# micron_P6.net
KiCad netlist of a schematic drawn in Altium Designer
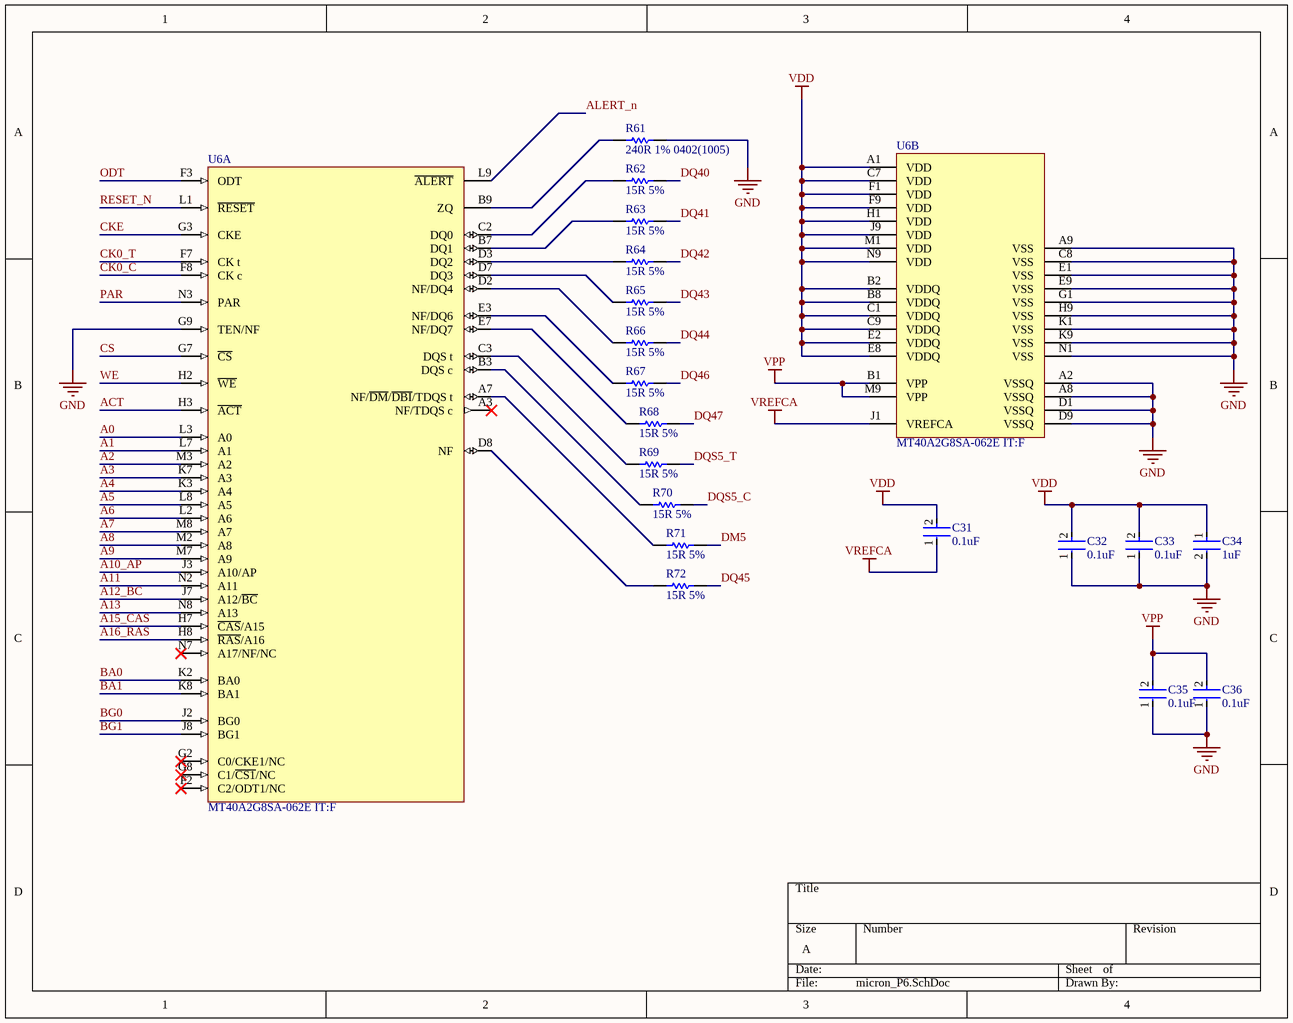
[diagram p0: micron_P6.SchDoc]

(export (version "E")
  (design (tool "Eeschema 10.0.6"))
  (components
    (comp (ref "C31")
      (value "0.1uF")
      (footprint "FP-GRM15-MFG")
      (description "CAP CER 0.1UF 16V X7R 0402")
      (fields (field (name "MANUFACTURER PART NUMBER") "GRM155R71C104KA88D") (field (name "TOLERANCE") "10%"))
      (libsource (lib "Altium Content Vault") (part "236180d848d6139a670b325ea6854c9"))
    )
    (comp (ref "C32")
      (value "0.1uF")
      (footprint "FP-GRM15-MFG")
      (description "CAP CER 0.1UF 16V X7R 0402")
      (fields (field (name "MANUFACTURER PART NUMBER") "GRM155R71C104KA88D") (field (name "TOLERANCE") "10%"))
      (libsource (lib "Altium Content Vault") (part "236180d848d6139a670b325ea6854c9"))
    )
    (comp (ref "C33")
      (value "0.1uF")
      (footprint "FP-GRM15-MFG")
      (description "CAP CER 0.1UF 16V X7R 0402")
      (fields (field (name "MANUFACTURER PART NUMBER") "GRM155R71C104KA88D") (field (name "TOLERANCE") "10%"))
      (libsource (lib "Altium Content Vault") (part "236180d848d6139a670b325ea6854c9"))
    )
    (comp (ref "C34")
      (value "1uF")
      (footprint "FP-CL511-IPC_C")
      (description "Cap Ceramic 1uF 10V X5R ±10% SMD 0402 +85°C Paper T/R")
      (fields (field (name "TOLERANCE") "10%"))
      (libsource (lib "Altium Content Vault") (part "b4654b650e69147ec39a6b967a45e02"))
    )
    (comp (ref "C35")
      (value "0.1uF")
      (footprint "FP-GRM15-MFG")
      (description "CAP CER 0.1UF 16V X7R 0402")
      (fields (field (name "MANUFACTURER PART NUMBER") "GRM155R71C104KA88D") (field (name "TOLERANCE") "10%"))
      (libsource (lib "Altium Content Vault") (part "236180d848d6139a670b325ea6854c9"))
    )
    (comp (ref "C36")
      (value "0.1uF")
      (footprint "FP-GRM15-MFG")
      (description "CAP CER 0.1UF 16V X7R 0402")
      (fields (field (name "MANUFACTURER PART NUMBER") "GRM155R71C104KA88D") (field (name "TOLERANCE") "10%"))
      (libsource (lib "Altium Content Vault") (part "236180d848d6139a670b325ea6854c9"))
    )
    (comp (ref "R61")
      (value "240R 1% 0402(1005)")
      (footprint "RESC0402(1005)_L")
      (description "240R 0.063W 1% 0402 (1005 Metric)  SMD")
      (fields (field (name "POWER") "0.063 W") (field (name "TOLERANCE") "1 %"))
      (libsource (lib "Altium Content Vault") (part "RES"))
    )
    (comp (ref "R62")
      (value "15R 5%")
      (footprint "RESC1005X40X25LL05T10")
      (fields (field (name "MANUFACTURER") "Yageo / Phycomp") (field (name "PART NUMBER") "RC0402FR-0715RL"))
      (libsource (lib "Altium Content Vault") (part "RES"))
    )
    (comp (ref "R63")
      (value "15R 5%")
      (footprint "RESC1005X40X25LL05T10")
      (fields (field (name "MANUFACTURER") "Yageo / Phycomp") (field (name "PART NUMBER") "RC0402FR-0715RL"))
      (libsource (lib "Altium Content Vault") (part "RES"))
    )
    (comp (ref "R64")
      (value "15R 5%")
      (footprint "RESC1005X40X25LL05T10")
      (fields (field (name "MANUFACTURER") "Yageo / Phycomp") (field (name "PART NUMBER") "RC0402FR-0715RL"))
      (libsource (lib "Altium Content Vault") (part "RES"))
    )
    (comp (ref "R65")
      (value "15R 5%")
      (footprint "RESC1005X40X25LL05T10")
      (fields (field (name "MANUFACTURER") "Yageo / Phycomp") (field (name "PART NUMBER") "RC0402FR-0715RL"))
      (libsource (lib "Altium Content Vault") (part "RES"))
    )
    (comp (ref "R66")
      (value "15R 5%")
      (footprint "RESC1005X40X25LL05T10")
      (fields (field (name "MANUFACTURER") "Yageo / Phycomp") (field (name "PART NUMBER") "RC0402FR-0715RL"))
      (libsource (lib "Altium Content Vault") (part "RES"))
    )
    (comp (ref "R67")
      (value "15R 5%")
      (footprint "RESC1005X40X25LL05T10")
      (fields (field (name "MANUFACTURER") "Yageo / Phycomp") (field (name "PART NUMBER") "RC0402FR-0715RL"))
      (libsource (lib "Altium Content Vault") (part "RES"))
    )
    (comp (ref "R68")
      (value "15R 5%")
      (footprint "RESC1005X40X25LL05T10")
      (fields (field (name "MANUFACTURER") "Yageo / Phycomp") (field (name "PART NUMBER") "RC0402FR-0715RL"))
      (libsource (lib "Altium Content Vault") (part "RES"))
    )
    (comp (ref "R69")
      (value "15R 5%")
      (footprint "RESC1005X40X25LL05T10")
      (fields (field (name "MANUFACTURER") "Yageo / Phycomp") (field (name "PART NUMBER") "RC0402FR-0715RL"))
      (libsource (lib "Altium Content Vault") (part "RES"))
    )
    (comp (ref "R70")
      (value "15R 5%")
      (footprint "RESC1005X40X25LL05T10")
      (fields (field (name "MANUFACTURER") "Yageo / Phycomp") (field (name "PART NUMBER") "RC0402FR-0715RL"))
      (libsource (lib "Altium Content Vault") (part "RES"))
    )
    (comp (ref "R71")
      (value "15R 5%")
      (footprint "RESC1005X40X25LL05T10")
      (fields (field (name "MANUFACTURER") "Yageo / Phycomp") (field (name "PART NUMBER") "RC0402FR-0715RL"))
      (libsource (lib "Altium Content Vault") (part "RES"))
    )
    (comp (ref "R72")
      (value "15R 5%")
      (footprint "RESC1005X40X25LL05T10")
      (fields (field (name "MANUFACTURER") "Yageo / Phycomp") (field (name "PART NUMBER") "RC0402FR-0715RL"))
      (libsource (lib "Altium Content Vault") (part "RES"))
    )
    (comp (ref "U6")
      (value "MT40A2G8SA-062E IT:F")
      (footprint "SA_MFG")
      (description "DRAMChip DDR4 SDRAM 16Gbit 2Gx8 1.2V 78-Pin FBGA Tray")
      (libsource (lib "Altium Content Vault") (part "d28cb998757b614ee3280f10a38a3b1"))
    )
  )
  (nets
    (net (code "1") (name "/A0") (class "Default")
      (node (ref "U6") (pin "L3") (pinfunction "A0_L3") (pintype "input"))
    )
    (net (code "2") (name "/A1") (class "Default")
      (node (ref "U6") (pin "L7") (pinfunction "A1_L7") (pintype "input"))
    )
    (net (code "3") (name "/A2") (class "Default")
      (node (ref "U6") (pin "M3") (pinfunction "A2_M3") (pintype "input"))
    )
    (net (code "4") (name "/A3") (class "Default")
      (node (ref "U6") (pin "K7") (pinfunction "A3_K7") (pintype "input"))
    )
    (net (code "5") (name "/A4") (class "Default")
      (node (ref "U6") (pin "K3") (pinfunction "A4_K3") (pintype "input"))
    )
    (net (code "6") (name "/A5") (class "Default")
      (node (ref "U6") (pin "L8") (pinfunction "A5_L8") (pintype "input"))
    )
    (net (code "7") (name "/A6") (class "Default")
      (node (ref "U6") (pin "L2") (pinfunction "A6_L2") (pintype "input"))
    )
    (net (code "8") (name "/A7") (class "Default")
      (node (ref "U6") (pin "M8") (pinfunction "A7_M8") (pintype "input"))
    )
    (net (code "9") (name "/A8") (class "Default")
      (node (ref "U6") (pin "M2") (pinfunction "A8_M2") (pintype "input"))
    )
    (net (code "10") (name "/A9") (class "Default")
      (node (ref "U6") (pin "M7") (pinfunction "A9_M7") (pintype "input"))
    )
    (net (code "11") (name "/A10_AP") (class "Default")
      (node (ref "U6") (pin "J3") (pinfunction "A10/AP_J3") (pintype "input"))
    )
    (net (code "12") (name "/A11") (class "Default")
      (node (ref "U6") (pin "N2") (pinfunction "A11_N2") (pintype "input"))
    )
    (net (code "13") (name "/A12_BC") (class "Default")
      (node (ref "U6") (pin "J7") (pinfunction "A12/~{BC}_J7") (pintype "input"))
    )
    (net (code "14") (name "/A13") (class "Default")
      (node (ref "U6") (pin "N8") (pinfunction "A13_N8") (pintype "input"))
    )
    (net (code "15") (name "/A15_CAS") (class "Default")
      (node (ref "U6") (pin "H7") (pinfunction "~{CAS}/A15_H7") (pintype "input"))
    )
    (net (code "16") (name "/A16_RAS") (class "Default")
      (node (ref "U6") (pin "H8") (pinfunction "~{RAS}/A16_H8") (pintype "input"))
    )
    (net (code "17") (name "/ACT") (class "Default")
      (node (ref "U6") (pin "H3") (pinfunction "~{ACT}_H3") (pintype "input"))
    )
    (net (code "18") (name "/ALERT_n") (class "Default")
      (node (ref "U6") (pin "L9") (pinfunction "~{ALERT}_L9") (pintype "open_collector"))
    )
    (net (code "19") (name "/BA0") (class "Default")
      (node (ref "U6") (pin "K2") (pinfunction "BA0_K2") (pintype "input"))
    )
    (net (code "20") (name "/BA1") (class "Default")
      (node (ref "U6") (pin "K8") (pinfunction "BA1_K8") (pintype "input"))
    )
    (net (code "21") (name "/BG0") (class "Default")
      (node (ref "U6") (pin "J2") (pinfunction "BG0_J2") (pintype "input"))
    )
    (net (code "22") (name "/BG1") (class "Default")
      (node (ref "U6") (pin "J8") (pinfunction "BG1_J8") (pintype "input"))
    )
    (net (code "23") (name "/CK0_C") (class "Default")
      (node (ref "U6") (pin "F8") (pinfunction "CK_c_F8") (pintype "input"))
    )
    (net (code "24") (name "/CK0_T") (class "Default")
      (node (ref "U6") (pin "F7") (pinfunction "CK_t_F7") (pintype "input"))
    )
    (net (code "25") (name "/CKE") (class "Default")
      (node (ref "U6") (pin "G3") (pinfunction "CKE_G3") (pintype "input"))
    )
    (net (code "26") (name "/CS") (class "Default")
      (node (ref "U6") (pin "G7") (pinfunction "~{CS}_G7") (pintype "input"))
    )
    (net (code "27") (name "/DM5") (class "Default")
      (node (ref "R71") (pin "2") (pinfunction "2_2") (pintype "passive"))
    )
    (net (code "28") (name "/DQ40") (class "Default")
      (node (ref "R62") (pin "2") (pinfunction "2_2") (pintype "passive"))
    )
    (net (code "29") (name "/DQ41") (class "Default")
      (node (ref "R63") (pin "2") (pinfunction "2_2") (pintype "passive"))
    )
    (net (code "30") (name "/DQ42") (class "Default")
      (node (ref "R64") (pin "2") (pinfunction "2_2") (pintype "passive"))
    )
    (net (code "31") (name "/DQ43") (class "Default")
      (node (ref "R65") (pin "2") (pinfunction "2_2") (pintype "passive"))
    )
    (net (code "32") (name "/DQ44") (class "Default")
      (node (ref "R66") (pin "2") (pinfunction "2_2") (pintype "passive"))
    )
    (net (code "33") (name "/DQ45") (class "Default")
      (node (ref "R72") (pin "2") (pinfunction "2_2") (pintype "passive"))
    )
    (net (code "34") (name "/DQ46") (class "Default")
      (node (ref "R67") (pin "2") (pinfunction "2_2") (pintype "passive"))
    )
    (net (code "35") (name "/DQ47") (class "Default")
      (node (ref "R68") (pin "2") (pinfunction "2_2") (pintype "passive"))
    )
    (net (code "36") (name "/DQS5_C") (class "Default")
      (node (ref "R70") (pin "2") (pinfunction "2_2") (pintype "passive"))
    )
    (net (code "37") (name "/DQS5_T") (class "Default")
      (node (ref "R69") (pin "2") (pinfunction "2_2") (pintype "passive"))
    )
    (net (code "38") (name "/ODT") (class "Default")
      (node (ref "U6") (pin "F3") (pinfunction "ODT_F3") (pintype "input"))
    )
    (net (code "39") (name "/PAR") (class "Default")
      (node (ref "U6") (pin "N3") (pinfunction "PAR_N3") (pintype "input"))
    )
    (net (code "40") (name "/RESET_N") (class "Default")
      (node (ref "U6") (pin "L1") (pinfunction "~{RESET}_L1") (pintype "input"))
    )
    (net (code "41") (name "/WE") (class "Default")
      (node (ref "U6") (pin "H2") (pinfunction "~{WE}_H2") (pintype "input"))
    )
    (net (code "42") (name "GND") (class "Default")
      (node (ref "C32") (pin "1") (pinfunction "1_1") (pintype "passive"))
      (node (ref "C33") (pin "1") (pinfunction "1_1") (pintype "passive"))
      (node (ref "C34") (pin "2") (pinfunction "2_2") (pintype "passive"))
      (node (ref "C35") (pin "1") (pinfunction "1_1") (pintype "passive"))
      (node (ref "C36") (pin "1") (pinfunction "1_1") (pintype "passive"))
      (node (ref "R61") (pin "2") (pinfunction "2_2") (pintype "passive"))
      (node (ref "U6") (pin "A2") (pinfunction "VSSQ_A2") (pintype "power_in"))
      (node (ref "U6") (pin "A8") (pinfunction "VSSQ_A8") (pintype "power_in"))
      (node (ref "U6") (pin "A9") (pinfunction "VSS_A9") (pintype "power_in"))
      (node (ref "U6") (pin "C8") (pinfunction "VSS_C8") (pintype "power_in"))
      (node (ref "U6") (pin "D1") (pinfunction "VSSQ_D1") (pintype "power_in"))
      (node (ref "U6") (pin "D9") (pinfunction "VSSQ_D9") (pintype "power_in"))
      (node (ref "U6") (pin "E1") (pinfunction "VSS_E1") (pintype "power_in"))
      (node (ref "U6") (pin "E9") (pinfunction "VSS_E9") (pintype "power_in"))
      (node (ref "U6") (pin "G1") (pinfunction "VSS_G1") (pintype "power_in"))
      (node (ref "U6") (pin "G9") (pinfunction "TEN/NF_G9") (pintype "input"))
      (node (ref "U6") (pin "H9") (pinfunction "VSS_H9") (pintype "power_in"))
      (node (ref "U6") (pin "K1") (pinfunction "VSS_K1") (pintype "power_in"))
      (node (ref "U6") (pin "K9") (pinfunction "VSS_K9") (pintype "power_in"))
      (node (ref "U6") (pin "N1") (pinfunction "VSS_N1") (pintype "power_in"))
    )
    (net (code "43") (name "Net-(U6A-DQ0)") (class "Default")
      (node (ref "R62") (pin "1") (pinfunction "1_1") (pintype "passive"))
      (node (ref "U6") (pin "C2") (pinfunction "DQ0_C2") (pintype "bidirectional"))
    )
    (net (code "44") (name "Net-(U6A-DQ1)") (class "Default")
      (node (ref "R63") (pin "1") (pinfunction "1_1") (pintype "passive"))
      (node (ref "U6") (pin "B7") (pinfunction "DQ1_B7") (pintype "bidirectional"))
    )
    (net (code "45") (name "Net-(U6A-DQ2)") (class "Default")
      (node (ref "R64") (pin "1") (pinfunction "1_1") (pintype "passive"))
      (node (ref "U6") (pin "D3") (pinfunction "DQ2_D3") (pintype "bidirectional"))
    )
    (net (code "46") (name "Net-(U6A-DQ3)") (class "Default")
      (node (ref "R65") (pin "1") (pinfunction "1_1") (pintype "passive"))
      (node (ref "U6") (pin "D7") (pinfunction "DQ3_D7") (pintype "bidirectional"))
    )
    (net (code "47") (name "Net-(U6A-DQS_c)") (class "Default")
      (node (ref "R70") (pin "1") (pinfunction "1_1") (pintype "passive"))
      (node (ref "U6") (pin "B3") (pinfunction "DQS_c_B3") (pintype "bidirectional"))
    )
    (net (code "48") (name "Net-(U6A-DQS_t)") (class "Default")
      (node (ref "R69") (pin "1") (pinfunction "1_1") (pintype "passive"))
      (node (ref "U6") (pin "C3") (pinfunction "DQS_t_C3") (pintype "bidirectional"))
    )
    (net (code "49") (name "Net-(U6A-NF)") (class "Default")
      (node (ref "R72") (pin "1") (pinfunction "1_1") (pintype "passive"))
      (node (ref "U6") (pin "D8") (pinfunction "NF_D8") (pintype "bidirectional"))
    )
    (net (code "50") (name "Net-(U6A-NF{slash}DQ4)") (class "Default")
      (node (ref "R66") (pin "1") (pinfunction "1_1") (pintype "passive"))
      (node (ref "U6") (pin "D2") (pinfunction "NF/DQ4_D2") (pintype "bidirectional"))
    )
    (net (code "51") (name "Net-(U6A-NF{slash}DQ6)") (class "Default")
      (node (ref "R67") (pin "1") (pinfunction "1_1") (pintype "passive"))
      (node (ref "U6") (pin "E3") (pinfunction "NF/DQ6_E3") (pintype "bidirectional"))
    )
    (net (code "52") (name "Net-(U6A-NF{slash}DQ7)") (class "Default")
      (node (ref "R68") (pin "1") (pinfunction "1_1") (pintype "passive"))
      (node (ref "U6") (pin "E7") (pinfunction "NF/DQ7_E7") (pintype "bidirectional"))
    )
    (net (code "53") (name "Net-(U6A-NF{slash}~{DM}{slash}~{DBI}{slash}TDQS_t)") (class "Default")
      (node (ref "R71") (pin "1") (pinfunction "1_1") (pintype "passive"))
      (node (ref "U6") (pin "A7") (pinfunction "NF/~{DM}/~{DBI}/TDQS_t_A7") (pintype "bidirectional"))
    )
    (net (code "54") (name "Net-(U6A-ZQ)") (class "Default")
      (node (ref "R61") (pin "1") (pinfunction "1_1") (pintype "passive"))
      (node (ref "U6") (pin "B9") (pinfunction "ZQ_B9") (pintype "passive"))
    )
    (net (code "55") (name "VDD") (class "Default")
      (node (ref "C31") (pin "2") (pinfunction "2_2") (pintype "passive"))
      (node (ref "C32") (pin "2") (pinfunction "2_2") (pintype "passive"))
      (node (ref "C33") (pin "2") (pinfunction "2_2") (pintype "passive"))
      (node (ref "C34") (pin "1") (pinfunction "1_1") (pintype "passive"))
      (node (ref "U6") (pin "A1") (pinfunction "VDD_A1") (pintype "power_in"))
      (node (ref "U6") (pin "B2") (pinfunction "VDDQ_B2") (pintype "power_in"))
      (node (ref "U6") (pin "B8") (pinfunction "VDDQ_B8") (pintype "power_in"))
      (node (ref "U6") (pin "C1") (pinfunction "VDDQ_C1") (pintype "power_in"))
      (node (ref "U6") (pin "C7") (pinfunction "VDD_C7") (pintype "power_in"))
      (node (ref "U6") (pin "C9") (pinfunction "VDDQ_C9") (pintype "power_in"))
      (node (ref "U6") (pin "E2") (pinfunction "VDDQ_E2") (pintype "power_in"))
      (node (ref "U6") (pin "E8") (pinfunction "VDDQ_E8") (pintype "power_in"))
      (node (ref "U6") (pin "F1") (pinfunction "VDD_F1") (pintype "power_in"))
      (node (ref "U6") (pin "F9") (pinfunction "VDD_F9") (pintype "power_in"))
      (node (ref "U6") (pin "H1") (pinfunction "VDD_H1") (pintype "power_in"))
      (node (ref "U6") (pin "J9") (pinfunction "VDD_J9") (pintype "power_in"))
      (node (ref "U6") (pin "M1") (pinfunction "VDD_M1") (pintype "power_in"))
      (node (ref "U6") (pin "N9") (pinfunction "VDD_N9") (pintype "power_in"))
    )
    (net (code "56") (name "VPP") (class "Default")
      (node (ref "C35") (pin "2") (pinfunction "2_2") (pintype "passive"))
      (node (ref "C36") (pin "2") (pinfunction "2_2") (pintype "passive"))
      (node (ref "U6") (pin "B1") (pinfunction "VPP_B1") (pintype "power_in"))
      (node (ref "U6") (pin "M9") (pinfunction "VPP_M9") (pintype "power_in"))
    )
    (net (code "57") (name "VREFCA") (class "Default")
      (node (ref "C31") (pin "1") (pinfunction "1_1") (pintype "passive"))
      (node (ref "U6") (pin "J1") (pinfunction "VREFCA_J1") (pintype "power_in"))
    )
    (net (code "58") (name "unconnected-(U6A-A17{slash}NF{slash}NC-PadN7)") (class "Default")
      (node (ref "U6") (pin "N7") (pinfunction "A17/NF/NC_N7") (pintype "input+no_connect"))
    )
    (net (code "59") (name "unconnected-(U6A-C0{slash}CKE1{slash}NC-PadG2)") (class "Default")
      (node (ref "U6") (pin "G2") (pinfunction "C0/CKE1/NC_G2") (pintype "input+no_connect"))
    )
    (net (code "60") (name "unconnected-(U6A-C1{slash}~{CS1}{slash}NC-PadG8)") (class "Default")
      (node (ref "U6") (pin "G8") (pinfunction "C1/~{CS1}/NC_G8") (pintype "input+no_connect"))
    )
    (net (code "61") (name "unconnected-(U6A-C2{slash}ODT1{slash}NC-PadF2)") (class "Default")
      (node (ref "U6") (pin "F2") (pinfunction "C2/ODT1/NC_F2") (pintype "input+no_connect"))
    )
    (net (code "62") (name "unconnected-(U6A-NF{slash}TDQS_c-PadA3)") (class "Default")
      (node (ref "U6") (pin "A3") (pinfunction "NF/TDQS_c_A3") (pintype "output+no_connect"))
    )
  )
)
